# QdecLogic.net
KiCad netlist of a schematic drawn in EAGLE
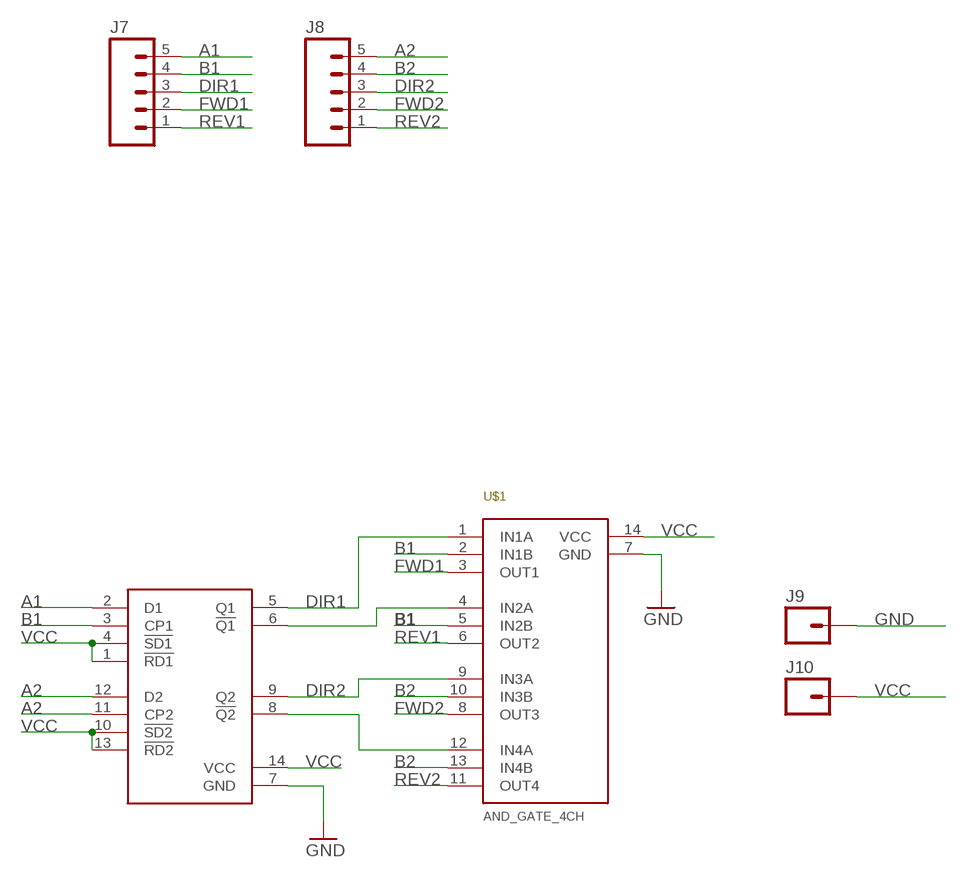
[diagram p0: schematic, sheet 1]

(export (version "E")
  (design (tool "Eeschema 10.0.6"))
  (components
    (comp (ref "J7")
      (value "M05NO_SILK")
      (footprint "eagle-import:1X05_NO_SILK")
      (libsource (lib "eagle-import") (part "M05NO_SILK"))
    )
    (comp (ref "J8")
      (value "M05NO_SILK")
      (footprint "eagle-import:1X05_NO_SILK")
      (libsource (lib "eagle-import") (part "M05NO_SILK"))
    )
    (comp (ref "J9")
      (value "M01PTH_NO_SILK_YES_STOP")
      (footprint "eagle-import:1X01_NO_SILK")
      (libsource (lib "eagle-import") (part "M01PTH_NO_SILK_YES_STOP"))
    )
    (comp (ref "J10")
      (value "M01PTH_NO_SILK_YES_STOP")
      (footprint "eagle-import:1X01_NO_SILK")
      (libsource (lib "eagle-import") (part "M01PTH_NO_SILK_YES_STOP"))
    )
    (comp (ref "U$1")
      (value "AND_GATE_4CH")
      (footprint "eagle-import:14-SOIC")
      (libsource (lib "eagle-import") (part "AND_GATE_4CH"))
    )
    (comp (ref "U$2")
      (value "FLIPFLOP_D-TYPE_2CH")
      (footprint "eagle-import:14-SOIC")
      (libsource (lib "eagle-import") (part "FLIPFLOP_D-TYPE_2CH"))
    )
  )
  (nets
    (net (code "1") (name "/A1") (class "Default")
      (node (ref "J7") (pin "5") (pinfunction "5_5") (pintype "passive"))
      (node (ref "U$2") (pin "2") (pinfunction "D1_2") (pintype "bidirectional"))
    )
    (net (code "2") (name "/A2") (class "Default")
      (node (ref "J8") (pin "5") (pinfunction "5_5") (pintype "passive"))
      (node (ref "U$2") (pin "12") (pinfunction "D2_12") (pintype "bidirectional"))
    )
    (net (code "3") (name "/B1") (class "Default")
      (node (ref "J7") (pin "4") (pinfunction "4_4") (pintype "passive"))
      (node (ref "U$1") (pin "2") (pinfunction "IN1B_2") (pintype "bidirectional"))
      (node (ref "U$1") (pin "5") (pinfunction "IN2B_5") (pintype "bidirectional"))
      (node (ref "U$2") (pin "3") (pinfunction "CP1_3") (pintype "bidirectional"))
    )
    (net (code "4") (name "/B2") (class "Default")
      (node (ref "J8") (pin "4") (pinfunction "4_4") (pintype "passive"))
      (node (ref "U$1") (pin "10") (pinfunction "IN3B_10") (pintype "bidirectional"))
      (node (ref "U$1") (pin "13") (pinfunction "IN4B_13") (pintype "bidirectional"))
      (node (ref "U$2") (pin "11") (pinfunction "CP2_11") (pintype "bidirectional"))
    )
    (net (code "5") (name "/DIR1") (class "Default")
      (node (ref "J7") (pin "3") (pinfunction "3_3") (pintype "passive"))
      (node (ref "U$1") (pin "1") (pinfunction "IN1A_1") (pintype "bidirectional"))
      (node (ref "U$2") (pin "5") (pinfunction "Q1_5") (pintype "bidirectional"))
    )
    (net (code "6") (name "/DIR2") (class "Default")
      (node (ref "J8") (pin "3") (pinfunction "3_3") (pintype "passive"))
      (node (ref "U$1") (pin "9") (pinfunction "IN3A_9") (pintype "bidirectional"))
      (node (ref "U$2") (pin "9") (pinfunction "Q2_9") (pintype "bidirectional"))
    )
    (net (code "7") (name "/FWD1") (class "Default")
      (node (ref "J7") (pin "2") (pinfunction "2_2") (pintype "passive"))
      (node (ref "U$1") (pin "3") (pinfunction "OUT1_3") (pintype "bidirectional"))
    )
    (net (code "8") (name "/FWD2") (class "Default")
      (node (ref "J8") (pin "2") (pinfunction "2_2") (pintype "passive"))
      (node (ref "U$1") (pin "8") (pinfunction "OUT3_8") (pintype "bidirectional"))
    )
    (net (code "9") (name "/REV1") (class "Default")
      (node (ref "J7") (pin "1") (pinfunction "1_1") (pintype "passive"))
      (node (ref "U$1") (pin "6") (pinfunction "OUT2_6") (pintype "bidirectional"))
    )
    (net (code "10") (name "/REV2") (class "Default")
      (node (ref "J8") (pin "1") (pinfunction "1_1") (pintype "passive"))
      (node (ref "U$1") (pin "11") (pinfunction "OUT4_11") (pintype "bidirectional"))
    )
    (net (code "11") (name "/VCC") (class "Default")
      (node (ref "J10") (pin "1") (pinfunction "1_1") (pintype "passive"))
      (node (ref "U$1") (pin "14") (pinfunction "VCC_14") (pintype "bidirectional"))
      (node (ref "U$2") (pin "1") (pinfunction "~{RD1}_1") (pintype "bidirectional"))
      (node (ref "U$2") (pin "10") (pinfunction "~{SD2}_10") (pintype "bidirectional"))
      (node (ref "U$2") (pin "13") (pinfunction "~{RD2}_13") (pintype "bidirectional"))
      (node (ref "U$2") (pin "14") (pinfunction "VCC_14") (pintype "bidirectional"))
      (node (ref "U$2") (pin "4") (pinfunction "~{SD1}_4") (pintype "bidirectional"))
    )
    (net (code "12") (name "GND") (class "Default")
      (node (ref "J9") (pin "1") (pinfunction "1_1") (pintype "passive"))
      (node (ref "U$1") (pin "7") (pinfunction "GND_7") (pintype "bidirectional"))
      (node (ref "U$2") (pin "7") (pinfunction "GND_7") (pintype "bidirectional"))
    )
    (net (code "13") (name "Net-(U$1-IN2A)") (class "Default")
      (node (ref "U$1") (pin "4") (pinfunction "IN2A_4") (pintype "bidirectional"))
      (node (ref "U$2") (pin "6") (pinfunction "~{Q1}_6") (pintype "bidirectional"))
    )
    (net (code "14") (name "Net-(U$1-IN4A)") (class "Default")
      (node (ref "U$1") (pin "12") (pinfunction "IN4A_12") (pintype "bidirectional"))
      (node (ref "U$2") (pin "8") (pinfunction "~{Q2}_8") (pintype "bidirectional"))
    )
  )
)
